# 780-00055_rev1B_CPLD_SCH_NRES_RTD_board.net
KiCad netlist of a schematic drawn in Altium Designer
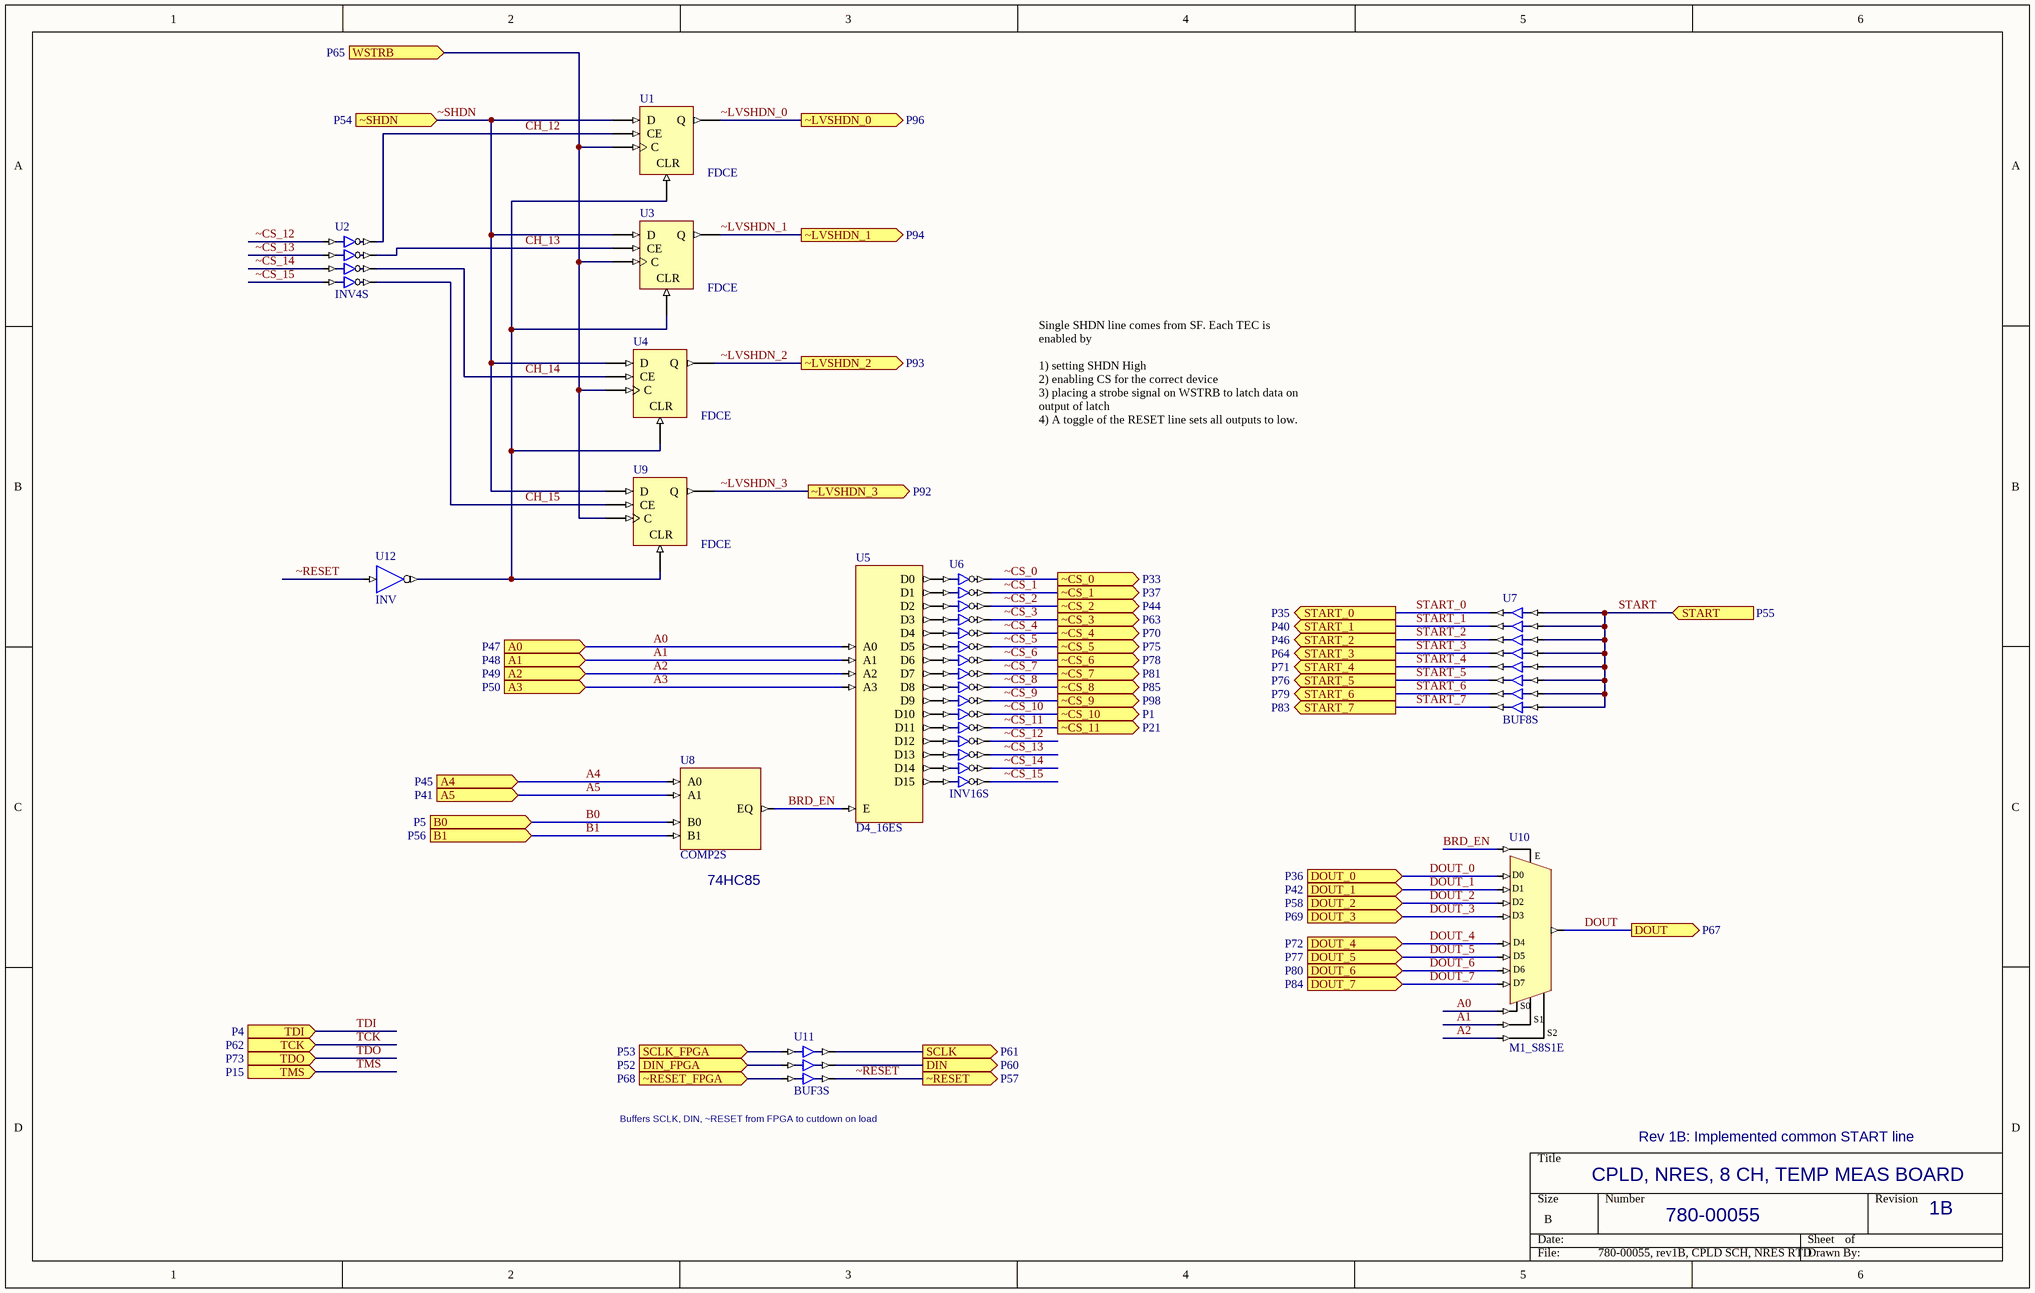
[diagram p0: 780-00055, rev1B, CPLD SCH, NRES RTD board.SchDoc]

(export (version "E")
  (design (tool "Eeschema 10.0.6"))
  (components
    (comp (ref "U1")
      (value "FDCE")
      (description "D Flip-Flop with Clock Enable and Asynchronous Clear")
      (fields (field (name "PUBLISHER") "Altium Limited"))
      (libsource (lib "Xilinx CoolRunner-XPLA3 FPGA") (part "FDCE"))
    )
    (comp (ref "U2")
      (value "INV4S")
      (description "4-Bit Inverter, Single Pin Version")
      (fields (field (name "PUBLISHER") "Altium Limited"))
      (libsource (lib "FPGA Generic") (part "INV4S"))
    )
    (comp (ref "U3")
      (value "FDCE")
      (description "D Flip-Flop with Clock Enable and Asynchronous Clear")
      (fields (field (name "PUBLISHER") "Altium Limited"))
      (libsource (lib "Xilinx CoolRunner-XPLA3 FPGA") (part "FDCE"))
    )
    (comp (ref "U4")
      (value "FDCE")
      (description "D Flip-Flop with Clock Enable and Asynchronous Clear")
      (fields (field (name "PUBLISHER") "Altium Limited"))
      (libsource (lib "Xilinx CoolRunner-XPLA3 FPGA") (part "FDCE"))
    )
    (comp (ref "U5")
      (value "D4_16ES")
      (description "Binary 4- to 16-Bit Decoder with Enable, Single Pin Version")
      (fields (field (name "PUBLISHER") "Altium Limited"))
      (libsource (lib "FPGA Generic") (part "D4_16ES"))
    )
    (comp (ref "U6")
      (value "INV16S")
      (description "16-Bit Inverter, Single Pin Version")
      (fields (field (name "PUBLISHER") "Altium Limited"))
      (libsource (lib "FPGA Generic") (part "INV16S"))
    )
    (comp (ref "U7")
      (value "BUF8S")
      (description "8-Bit General Purpose (Non-inverting) Buffer, Single Pin Version")
      (fields (field (name "PUBLISHER") "Altium Limited"))
      (libsource (lib "FPGA Generic") (part "BUF8S"))
    )
    (comp (ref "U8")
      (value "COMP2S")
      (description "2-Bit Identity Comparator, Single Pin Version")
      (fields (field (name "PUBLISHER") "Altium Limited"))
      (libsource (lib "FPGA Generic") (part "COMP2S"))
    )
    (comp (ref "U9")
      (value "FDCE")
      (description "D Flip-Flop with Clock Enable and Asynchronous Clear")
      (fields (field (name "PUBLISHER") "Altium Limited"))
      (libsource (lib "Xilinx CoolRunner-XPLA3 FPGA") (part "FDCE"))
    )
    (comp (ref "U10")
      (value "M1_S8S1E")
      (description "8x1-Single Wire to 1x1-Single Wire Multiplexer With Enable")
      (fields (field (name "PUBLISHER") "Altium Limited"))
      (libsource (lib "FPGA Generic") (part "M1_S8S1E"))
    )
    (comp (ref "U11")
      (value "BUF3S")
      (description "3-Bit General Purpose (Non-inverting) Buffer, Single Pin Version")
      (fields (field (name "PUBLISHER") "Altium Limited"))
      (libsource (lib "FPGA Generic") (part "BUF3S"))
    )
    (comp (ref "U12")
      (value "INV")
      (description "Inverter")
      (fields (field (name "PUBLISHER") "Altium Limited"))
      (libsource (lib "FPGA Generic") (part "INV"))
    )
  )
  (nets
    (net (code "1") (name "/A0") (class "Default")
      (node (ref "U10") (pin "S0") (pinfunction "S0_S0") (pintype "input"))
      (node (ref "U5") (pin "A0") (pinfunction "A0_A0") (pintype "input"))
    )
    (net (code "2") (name "/A1") (class "Default")
      (node (ref "U10") (pin "S1") (pinfunction "S1_S1") (pintype "input"))
      (node (ref "U5") (pin "A1") (pinfunction "A1_A1") (pintype "input"))
    )
    (net (code "3") (name "/A2") (class "Default")
      (node (ref "U10") (pin "S2") (pinfunction "S2_S2") (pintype "input"))
      (node (ref "U5") (pin "A2") (pinfunction "A2_A2") (pintype "input"))
    )
    (net (code "4") (name "/A3") (class "Default")
      (node (ref "U5") (pin "A3") (pinfunction "A3_A3") (pintype "input"))
    )
    (net (code "5") (name "/A4") (class "Default")
      (node (ref "U8") (pin "A0") (pinfunction "A0_A0") (pintype "input"))
    )
    (net (code "6") (name "/A5") (class "Default")
      (node (ref "U8") (pin "A1") (pinfunction "A1_A1") (pintype "input"))
    )
    (net (code "7") (name "/B0") (class "Default")
      (node (ref "U8") (pin "B0") (pinfunction "B0_B0") (pintype "input"))
    )
    (net (code "8") (name "/B1") (class "Default")
      (node (ref "U8") (pin "B1") (pinfunction "B1_B1") (pintype "input"))
    )
    (net (code "9") (name "/BRD_EN") (class "Default")
      (node (ref "U10") (pin "E") (pinfunction "E_E") (pintype "input"))
      (node (ref "U5") (pin "E") (pinfunction "E_E") (pintype "input"))
      (node (ref "U8") (pin "EQ") (pinfunction "EQ_EQ") (pintype "output"))
    )
    (net (code "10") (name "/CH_12") (class "Default")
      (node (ref "U1") (pin "CE") (pinfunction "CE_CE") (pintype "input"))
      (node (ref "U2") (pin "O0") (pinfunction "O0_O0") (pintype "output"))
    )
    (net (code "11") (name "/CH_13") (class "Default")
      (node (ref "U2") (pin "O1") (pinfunction "O1_O1") (pintype "output"))
      (node (ref "U3") (pin "CE") (pinfunction "CE_CE") (pintype "input"))
    )
    (net (code "12") (name "/CH_14") (class "Default")
      (node (ref "U2") (pin "O2") (pinfunction "O2_O2") (pintype "output"))
      (node (ref "U4") (pin "CE") (pinfunction "CE_CE") (pintype "input"))
    )
    (net (code "13") (name "/CH_15") (class "Default")
      (node (ref "U2") (pin "O3") (pinfunction "O3_O3") (pintype "output"))
      (node (ref "U9") (pin "CE") (pinfunction "CE_CE") (pintype "input"))
    )
    (net (code "14") (name "/DIN") (class "Default")
      (node (ref "U11") (pin "O1") (pinfunction "O1_O1") (pintype "output"))
    )
    (net (code "15") (name "/DIN_FPGA") (class "Default")
      (node (ref "U11") (pin "I1") (pinfunction "I1_I1") (pintype "input"))
    )
    (net (code "16") (name "/DOUT") (class "Default")
      (node (ref "U10") (pin "O") (pinfunction "O_O") (pintype "output"))
    )
    (net (code "17") (name "/DOUT_0") (class "Default")
      (node (ref "U10") (pin "D0") (pinfunction "D0_D0") (pintype "input"))
    )
    (net (code "18") (name "/DOUT_1") (class "Default")
      (node (ref "U10") (pin "D1") (pinfunction "D1_D1") (pintype "input"))
    )
    (net (code "19") (name "/DOUT_2") (class "Default")
      (node (ref "U10") (pin "D2") (pinfunction "D2_D2") (pintype "input"))
    )
    (net (code "20") (name "/DOUT_3") (class "Default")
      (node (ref "U10") (pin "D3") (pinfunction "D3_D3") (pintype "input"))
    )
    (net (code "21") (name "/DOUT_4") (class "Default")
      (node (ref "U10") (pin "D4") (pinfunction "D4_D4") (pintype "input"))
    )
    (net (code "22") (name "/DOUT_5") (class "Default")
      (node (ref "U10") (pin "D5") (pinfunction "D5_D5") (pintype "input"))
    )
    (net (code "23") (name "/DOUT_6") (class "Default")
      (node (ref "U10") (pin "D6") (pinfunction "D6_D6") (pintype "input"))
    )
    (net (code "24") (name "/DOUT_7") (class "Default")
      (node (ref "U10") (pin "D7") (pinfunction "D7_D7") (pintype "input"))
    )
    (net (code "25") (name "/SCLK") (class "Default")
      (node (ref "U11") (pin "O0") (pinfunction "O0_O0") (pintype "output"))
    )
    (net (code "26") (name "/SCLK_FPGA") (class "Default")
      (node (ref "U11") (pin "I0") (pinfunction "I0_I0") (pintype "input"))
    )
    (net (code "27") (name "/START") (class "Default")
      (node (ref "U7") (pin "I0") (pinfunction "I0_I0") (pintype "input"))
      (node (ref "U7") (pin "I1") (pinfunction "I1_I1") (pintype "input"))
      (node (ref "U7") (pin "I2") (pinfunction "I2_I2") (pintype "input"))
      (node (ref "U7") (pin "I3") (pinfunction "I3_I3") (pintype "input"))
      (node (ref "U7") (pin "I4") (pinfunction "I4_I4") (pintype "input"))
      (node (ref "U7") (pin "I5") (pinfunction "I5_I5") (pintype "input"))
      (node (ref "U7") (pin "I6") (pinfunction "I6_I6") (pintype "input"))
      (node (ref "U7") (pin "I7") (pinfunction "I7_I7") (pintype "input"))
    )
    (net (code "28") (name "/START_0") (class "Default")
      (node (ref "U7") (pin "O7") (pinfunction "O7_O7") (pintype "output"))
    )
    (net (code "29") (name "/START_1") (class "Default")
      (node (ref "U7") (pin "O6") (pinfunction "O6_O6") (pintype "output"))
    )
    (net (code "30") (name "/START_2") (class "Default")
      (node (ref "U7") (pin "O5") (pinfunction "O5_O5") (pintype "output"))
    )
    (net (code "31") (name "/START_3") (class "Default")
      (node (ref "U7") (pin "O4") (pinfunction "O4_O4") (pintype "output"))
    )
    (net (code "32") (name "/START_4") (class "Default")
      (node (ref "U7") (pin "O3") (pinfunction "O3_O3") (pintype "output"))
    )
    (net (code "33") (name "/START_5") (class "Default")
      (node (ref "U7") (pin "O2") (pinfunction "O2_O2") (pintype "output"))
    )
    (net (code "34") (name "/START_6") (class "Default")
      (node (ref "U7") (pin "O1") (pinfunction "O1_O1") (pintype "output"))
    )
    (net (code "35") (name "/START_7") (class "Default")
      (node (ref "U7") (pin "O0") (pinfunction "O0_O0") (pintype "output"))
    )
    (net (code "40") (name "/WSTRB") (class "Default")
      (node (ref "U1") (pin "C") (pinfunction "C_C") (pintype "input"))
      (node (ref "U3") (pin "C") (pinfunction "C_C") (pintype "input"))
      (node (ref "U4") (pin "C") (pinfunction "C_C") (pintype "input"))
      (node (ref "U9") (pin "C") (pinfunction "C_C") (pintype "input"))
    )
    (net (code "41") (name "/~CS_0") (class "Default")
      (node (ref "U6") (pin "O0") (pinfunction "O0_O0") (pintype "output"))
    )
    (net (code "42") (name "/~CS_1") (class "Default")
      (node (ref "U6") (pin "O1") (pinfunction "O1_O1") (pintype "output"))
    )
    (net (code "43") (name "/~CS_2") (class "Default")
      (node (ref "U6") (pin "O2") (pinfunction "O2_O2") (pintype "output"))
    )
    (net (code "44") (name "/~CS_3") (class "Default")
      (node (ref "U6") (pin "O3") (pinfunction "O3_O3") (pintype "output"))
    )
    (net (code "45") (name "/~CS_4") (class "Default")
      (node (ref "U6") (pin "O4") (pinfunction "O4_O4") (pintype "output"))
    )
    (net (code "46") (name "/~CS_5") (class "Default")
      (node (ref "U6") (pin "O5") (pinfunction "O5_O5") (pintype "output"))
    )
    (net (code "47") (name "/~CS_6") (class "Default")
      (node (ref "U6") (pin "O6") (pinfunction "O6_O6") (pintype "output"))
    )
    (net (code "48") (name "/~CS_7") (class "Default")
      (node (ref "U6") (pin "O7") (pinfunction "O7_O7") (pintype "output"))
    )
    (net (code "49") (name "/~CS_8") (class "Default")
      (node (ref "U6") (pin "O8") (pinfunction "O8_O8") (pintype "output"))
    )
    (net (code "50") (name "/~CS_9") (class "Default")
      (node (ref "U6") (pin "O9") (pinfunction "O9_O9") (pintype "output"))
    )
    (net (code "51") (name "/~CS_10") (class "Default")
      (node (ref "U6") (pin "O10") (pinfunction "O10_O10") (pintype "output"))
    )
    (net (code "52") (name "/~CS_11") (class "Default")
      (node (ref "U6") (pin "O11") (pinfunction "O11_O11") (pintype "output"))
    )
    (net (code "53") (name "/~CS_12") (class "Default")
      (node (ref "U2") (pin "I0") (pinfunction "I0_I0") (pintype "input"))
      (node (ref "U6") (pin "O12") (pinfunction "O12_O12") (pintype "output"))
    )
    (net (code "54") (name "/~CS_13") (class "Default")
      (node (ref "U2") (pin "I1") (pinfunction "I1_I1") (pintype "input"))
      (node (ref "U6") (pin "O13") (pinfunction "O13_O13") (pintype "output"))
    )
    (net (code "55") (name "/~CS_14") (class "Default")
      (node (ref "U2") (pin "I2") (pinfunction "I2_I2") (pintype "input"))
      (node (ref "U6") (pin "O14") (pinfunction "O14_O14") (pintype "output"))
    )
    (net (code "56") (name "/~CS_15") (class "Default")
      (node (ref "U2") (pin "I3") (pinfunction "I3_I3") (pintype "input"))
      (node (ref "U6") (pin "O15") (pinfunction "O15_O15") (pintype "output"))
    )
    (net (code "57") (name "/~LVSHDN_0") (class "Default")
      (node (ref "U1") (pin "Q") (pinfunction "Q_Q") (pintype "output"))
    )
    (net (code "58") (name "/~LVSHDN_1") (class "Default")
      (node (ref "U3") (pin "Q") (pinfunction "Q_Q") (pintype "output"))
    )
    (net (code "59") (name "/~LVSHDN_2") (class "Default")
      (node (ref "U4") (pin "Q") (pinfunction "Q_Q") (pintype "output"))
    )
    (net (code "60") (name "/~LVSHDN_3") (class "Default")
      (node (ref "U9") (pin "Q") (pinfunction "Q_Q") (pintype "output"))
    )
    (net (code "61") (name "/~RESET") (class "Default")
      (node (ref "U11") (pin "O2") (pinfunction "O2_O2") (pintype "output"))
      (node (ref "U12") (pin "I") (pinfunction "I_I") (pintype "input"))
    )
    (net (code "62") (name "/~RESET_FPGA") (class "Default")
      (node (ref "U11") (pin "I2") (pinfunction "I2_I2") (pintype "input"))
    )
    (net (code "63") (name "/~SHDN") (class "Default")
      (node (ref "U1") (pin "D") (pinfunction "D_D") (pintype "input"))
      (node (ref "U3") (pin "D") (pinfunction "D_D") (pintype "input"))
      (node (ref "U4") (pin "D") (pinfunction "D_D") (pintype "input"))
      (node (ref "U9") (pin "D") (pinfunction "D_D") (pintype "input"))
    )
    (net (code "64") (name "Net-(U1-PadCLR)") (class "Default")
      (node (ref "U1") (pin "CLR") (pinfunction "CLR_CLR") (pintype "input"))
      (node (ref "U12") (pin "O") (pinfunction "O_O") (pintype "output"))
      (node (ref "U3") (pin "CLR") (pinfunction "CLR_CLR") (pintype "input"))
      (node (ref "U4") (pin "CLR") (pinfunction "CLR_CLR") (pintype "input"))
      (node (ref "U9") (pin "CLR") (pinfunction "CLR_CLR") (pintype "input"))
    )
    (net (code "65") (name "Net-(U5-PadD0)") (class "Default")
      (node (ref "U5") (pin "D0") (pinfunction "D0_D0") (pintype "output"))
      (node (ref "U6") (pin "I0") (pinfunction "I0_I0") (pintype "input"))
    )
    (net (code "66") (name "Net-(U5-PadD1)") (class "Default")
      (node (ref "U5") (pin "D1") (pinfunction "D1_D1") (pintype "output"))
      (node (ref "U6") (pin "I1") (pinfunction "I1_I1") (pintype "input"))
    )
    (net (code "67") (name "Net-(U5-PadD2)") (class "Default")
      (node (ref "U5") (pin "D2") (pinfunction "D2_D2") (pintype "output"))
      (node (ref "U6") (pin "I2") (pinfunction "I2_I2") (pintype "input"))
    )
    (net (code "68") (name "Net-(U5-PadD3)") (class "Default")
      (node (ref "U5") (pin "D3") (pinfunction "D3_D3") (pintype "output"))
      (node (ref "U6") (pin "I3") (pinfunction "I3_I3") (pintype "input"))
    )
    (net (code "69") (name "Net-(U5-PadD4)") (class "Default")
      (node (ref "U5") (pin "D4") (pinfunction "D4_D4") (pintype "output"))
      (node (ref "U6") (pin "I4") (pinfunction "I4_I4") (pintype "input"))
    )
    (net (code "70") (name "Net-(U5-PadD5)") (class "Default")
      (node (ref "U5") (pin "D5") (pinfunction "D5_D5") (pintype "output"))
      (node (ref "U6") (pin "I5") (pinfunction "I5_I5") (pintype "input"))
    )
    (net (code "71") (name "Net-(U5-PadD6)") (class "Default")
      (node (ref "U5") (pin "D6") (pinfunction "D6_D6") (pintype "output"))
      (node (ref "U6") (pin "I6") (pinfunction "I6_I6") (pintype "input"))
    )
    (net (code "72") (name "Net-(U5-PadD7)") (class "Default")
      (node (ref "U5") (pin "D7") (pinfunction "D7_D7") (pintype "output"))
      (node (ref "U6") (pin "I7") (pinfunction "I7_I7") (pintype "input"))
    )
    (net (code "73") (name "Net-(U5-PadD8)") (class "Default")
      (node (ref "U5") (pin "D8") (pinfunction "D8_D8") (pintype "output"))
      (node (ref "U6") (pin "I8") (pinfunction "I8_I8") (pintype "input"))
    )
    (net (code "74") (name "Net-(U5-PadD9)") (class "Default")
      (node (ref "U5") (pin "D9") (pinfunction "D9_D9") (pintype "output"))
      (node (ref "U6") (pin "I9") (pinfunction "I9_I9") (pintype "input"))
    )
    (net (code "75") (name "Net-(U5-PadD10)") (class "Default")
      (node (ref "U5") (pin "D10") (pinfunction "D10_D10") (pintype "output"))
      (node (ref "U6") (pin "I10") (pinfunction "I10_I10") (pintype "input"))
    )
    (net (code "76") (name "Net-(U5-PadD11)") (class "Default")
      (node (ref "U5") (pin "D11") (pinfunction "D11_D11") (pintype "output"))
      (node (ref "U6") (pin "I11") (pinfunction "I11_I11") (pintype "input"))
    )
    (net (code "77") (name "Net-(U5-PadD12)") (class "Default")
      (node (ref "U5") (pin "D12") (pinfunction "D12_D12") (pintype "output"))
      (node (ref "U6") (pin "I12") (pinfunction "I12_I12") (pintype "input"))
    )
    (net (code "78") (name "Net-(U5-PadD13)") (class "Default")
      (node (ref "U5") (pin "D13") (pinfunction "D13_D13") (pintype "output"))
      (node (ref "U6") (pin "I13") (pinfunction "I13_I13") (pintype "input"))
    )
    (net (code "79") (name "Net-(U5-PadD14)") (class "Default")
      (node (ref "U5") (pin "D14") (pinfunction "D14_D14") (pintype "output"))
      (node (ref "U6") (pin "I14") (pinfunction "I14_I14") (pintype "input"))
    )
    (net (code "80") (name "Net-(U5-PadD15)") (class "Default")
      (node (ref "U5") (pin "D15") (pinfunction "D15_D15") (pintype "output"))
      (node (ref "U6") (pin "I15") (pinfunction "I15_I15") (pintype "input"))
    )
  )
)
